# Connectors.net
KiCad netlist of a schematic drawn in Altium Designer
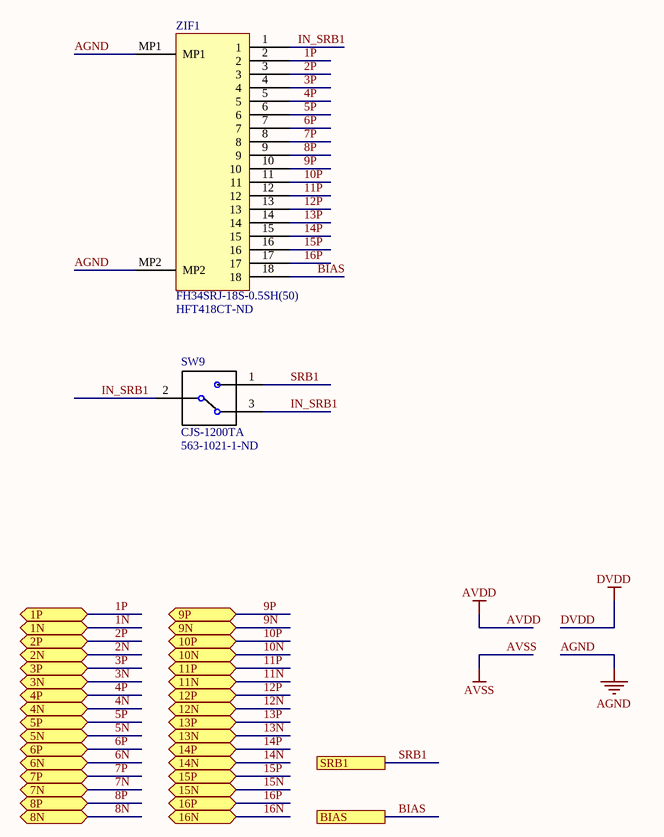
[diagram p0: Connectors.SchDoc]

(export (version "E")
  (design (tool "Eeschema 10.0.6"))
  (components
    (comp (ref "SW9")
      (value "CJS-1200TA")
      (footprint "*SW_CJS-1200TA")
      (description "SWITCH SLIDE SPDT 100MA 6V")
      (fields (field (name "SUPPLIER PART NUMBER 1") "563-1021-1-ND"))
      (libsource (lib "EE_smallOB_BW_v1.0") (part "CJS-1200TA"))
    )
    (comp (ref "ZIF1")
      (value "FH34SRJ-18S-0.5SH(50)")
      (footprint "ZIF_18S")
      (description "CONN FFC FPC 18POS 0.50MM R/A")
      (fields (field (name "SUPPLIER PART NUMBER 1") "HFT418CT-ND"))
      (libsource (lib "EE_smallOB_BW_v1.0") (part "FH34SRJ-18S-0.5SH(50)"))
    )
  )
  (nets
    (net (code "2") (name "/1P") (class "Default")
      (node (ref "ZIF1") (pin "2") (pinfunction "2_2") (pintype "passive"))
    )
    (net (code "4") (name "/2P") (class "Default")
      (node (ref "ZIF1") (pin "3") (pinfunction "3_3") (pintype "passive"))
    )
    (net (code "6") (name "/3P") (class "Default")
      (node (ref "ZIF1") (pin "4") (pinfunction "4_4") (pintype "passive"))
    )
    (net (code "8") (name "/4P") (class "Default")
      (node (ref "ZIF1") (pin "5") (pinfunction "5_5") (pintype "passive"))
    )
    (net (code "10") (name "/5P") (class "Default")
      (node (ref "ZIF1") (pin "6") (pinfunction "6_6") (pintype "passive"))
    )
    (net (code "12") (name "/6P") (class "Default")
      (node (ref "ZIF1") (pin "7") (pinfunction "7_7") (pintype "passive"))
    )
    (net (code "14") (name "/7P") (class "Default")
      (node (ref "ZIF1") (pin "8") (pinfunction "8_8") (pintype "passive"))
    )
    (net (code "16") (name "/8P") (class "Default")
      (node (ref "ZIF1") (pin "9") (pinfunction "9_9") (pintype "passive"))
    )
    (net (code "18") (name "/9P") (class "Default")
      (node (ref "ZIF1") (pin "10") (pinfunction "10_10") (pintype "passive"))
    )
    (net (code "20") (name "/10P") (class "Default")
      (node (ref "ZIF1") (pin "11") (pinfunction "11_11") (pintype "passive"))
    )
    (net (code "22") (name "/11P") (class "Default")
      (node (ref "ZIF1") (pin "12") (pinfunction "12_12") (pintype "passive"))
    )
    (net (code "24") (name "/12P") (class "Default")
      (node (ref "ZIF1") (pin "13") (pinfunction "13_13") (pintype "passive"))
    )
    (net (code "26") (name "/13P") (class "Default")
      (node (ref "ZIF1") (pin "14") (pinfunction "14_14") (pintype "passive"))
    )
    (net (code "28") (name "/14P") (class "Default")
      (node (ref "ZIF1") (pin "15") (pinfunction "15_15") (pintype "passive"))
    )
    (net (code "30") (name "/15P") (class "Default")
      (node (ref "ZIF1") (pin "16") (pinfunction "16_16") (pintype "passive"))
    )
    (net (code "32") (name "/16P") (class "Default")
      (node (ref "ZIF1") (pin "17") (pinfunction "17_17") (pintype "passive"))
    )
    (net (code "33") (name "/BIAS") (class "Default")
      (node (ref "ZIF1") (pin "18") (pinfunction "18_18") (pintype "passive"))
    )
    (net (code "34") (name "/IN_SRB1") (class "Default")
      (node (ref "SW9") (pin "2") (pinfunction "2_2") (pintype "passive"))
      (node (ref "SW9") (pin "3") (pinfunction "3_3") (pintype "passive"))
      (node (ref "ZIF1") (pin "1") (pinfunction "1_1") (pintype "passive"))
    )
    (net (code "35") (name "/SRB1") (class "Default")
      (node (ref "SW9") (pin "1") (pinfunction "1_1") (pintype "passive"))
    )
    (net (code "36") (name "AGND") (class "Default")
      (node (ref "ZIF1") (pin "MP1") (pinfunction "MP1_MP1") (pintype "passive"))
      (node (ref "ZIF1") (pin "MP2") (pinfunction "MP2_MP2") (pintype "passive"))
    )
  )
)
